# Power_Board.net
KiCad netlist of a schematic drawn in EAGLE
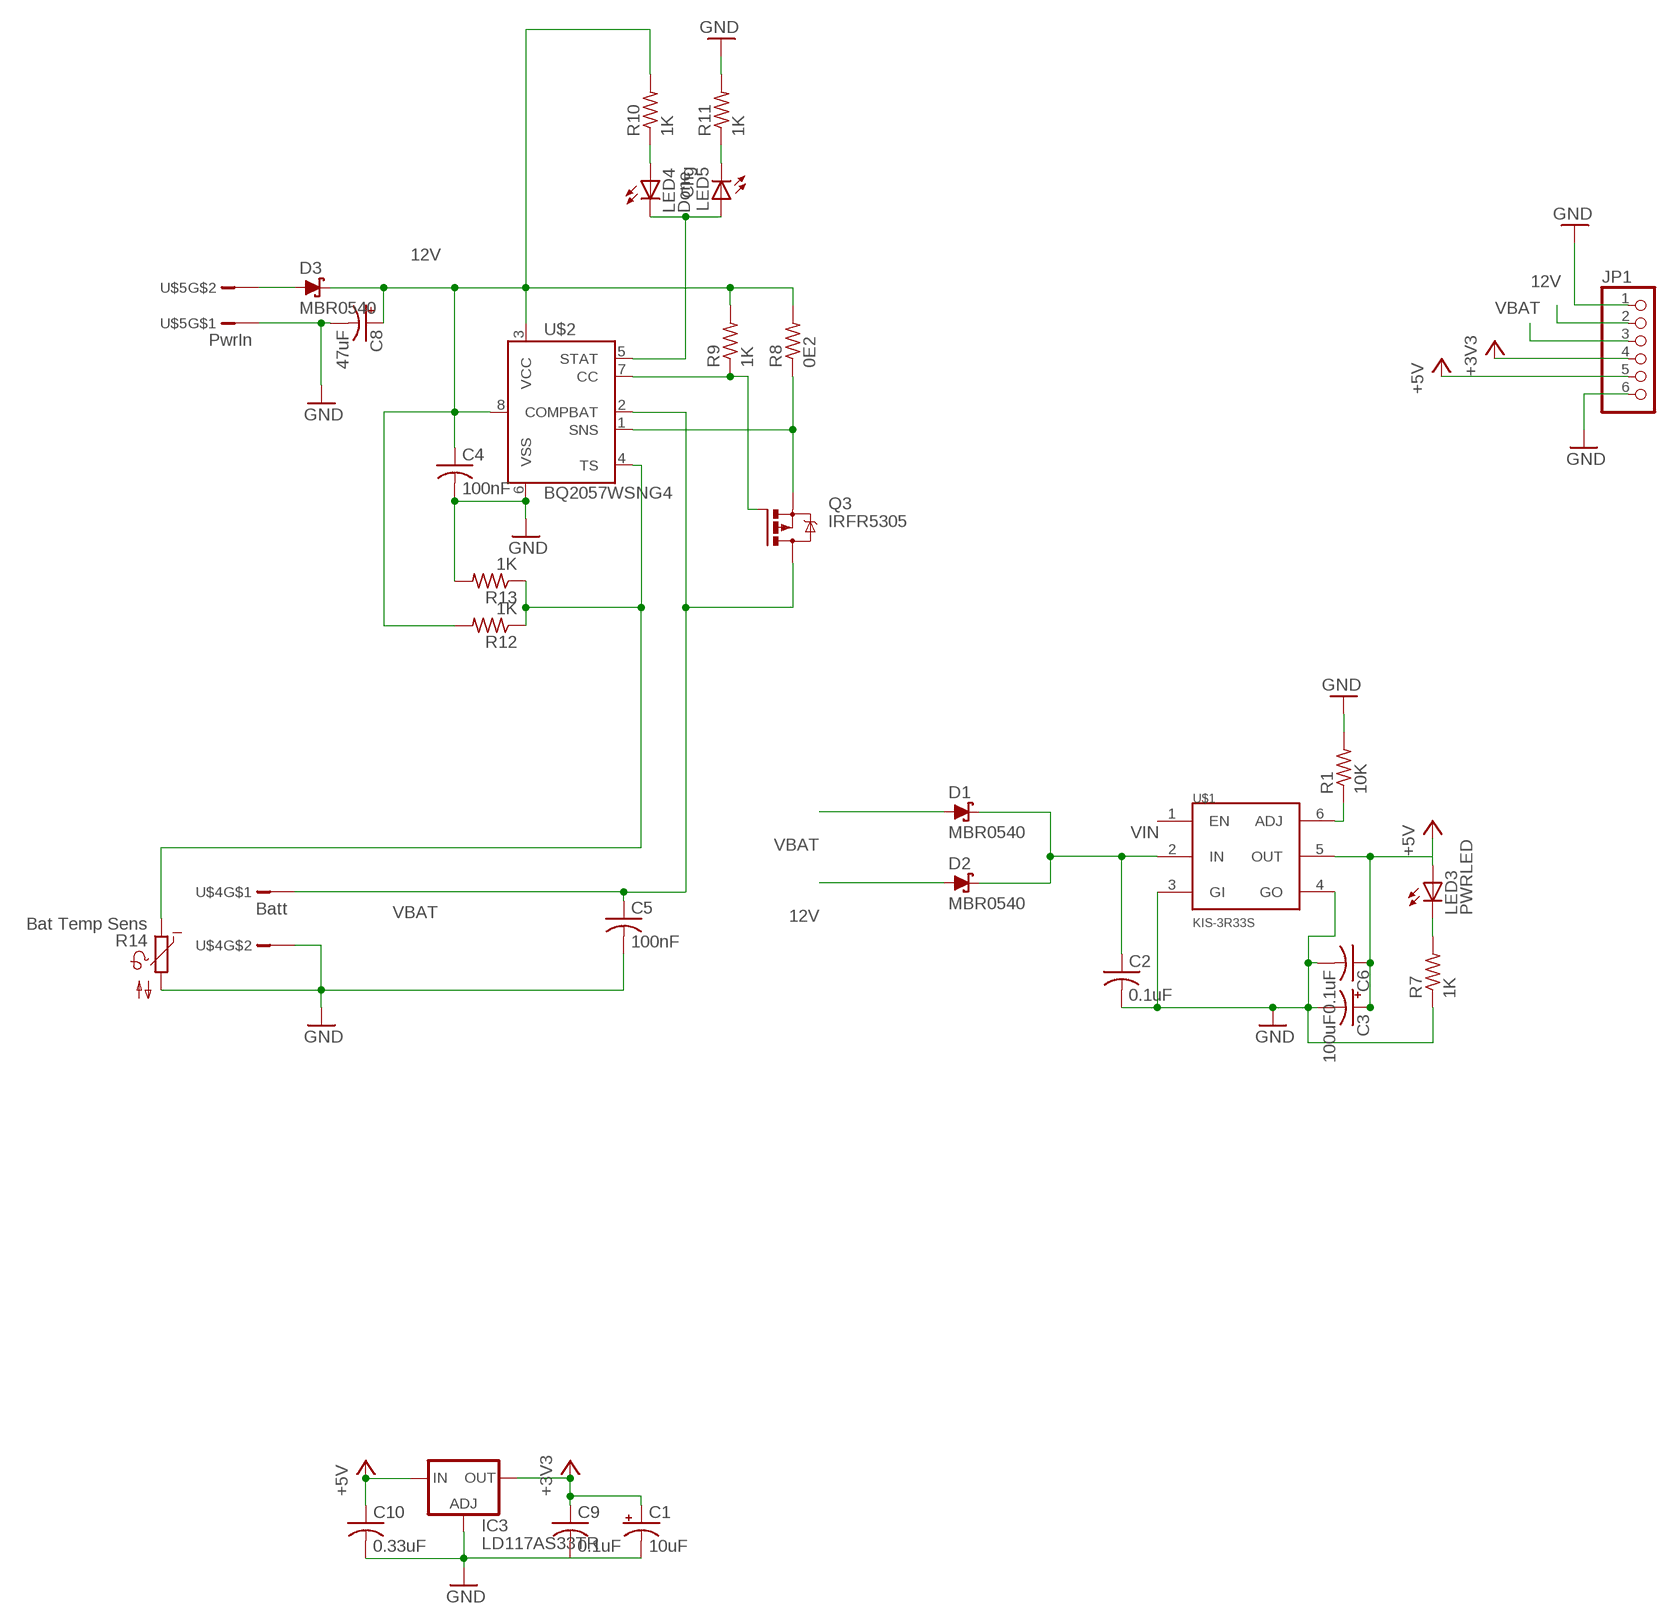
[diagram p0: schematic, sheet 1]

(export (version "E")
  (design (tool "Eeschema 10.0.6"))
  (components
    (comp (ref "C1")
      (value "10uF")
      (footprint "eagle-import:E2,5-7")
      (libsource (lib "eagle-import") (part "CPOL-USE2.5-7"))
    )
    (comp (ref "C2")
      (value "0.1uF")
      (footprint "eagle-import:C0805K")
      (libsource (lib "eagle-import") (part "C-USC0805K"))
    )
    (comp (ref "C3")
      (value "100uF")
      (footprint "eagle-import:E2,5-7")
      (libsource (lib "eagle-import") (part "CPOL-USE2.5-7"))
    )
    (comp (ref "C4")
      (value "100nF")
      (footprint "eagle-import:C0805K")
      (libsource (lib "eagle-import") (part "C-USC0805K"))
    )
    (comp (ref "C5")
      (value "100nF")
      (footprint "eagle-import:C0805K")
      (libsource (lib "eagle-import") (part "C-USC0805K"))
    )
    (comp (ref "C6")
      (value "0.1uF")
      (footprint "eagle-import:C0805K")
      (libsource (lib "eagle-import") (part "C-USC0805K"))
    )
    (comp (ref "C8")
      (value "47uF")
      (footprint "eagle-import:E2,5-7")
      (libsource (lib "eagle-import") (part "CPOL-USE2.5-7"))
    )
    (comp (ref "C9")
      (value "0.1uF")
      (footprint "eagle-import:C0805K")
      (libsource (lib "eagle-import") (part "C-USC0805K"))
    )
    (comp (ref "C10")
      (value "0.33uF")
      (footprint "eagle-import:C0805K")
      (libsource (lib "eagle-import") (part "C-USC0805K"))
    )
    (comp (ref "D1")
      (value "MBR0540")
      (footprint "eagle-import:SOD123")
      (libsource (lib "eagle-import") (part "MBR0540"))
    )
    (comp (ref "D2")
      (value "MBR0540")
      (footprint "eagle-import:SOD123")
      (libsource (lib "eagle-import") (part "MBR0540"))
    )
    (comp (ref "D3")
      (value "MBR0540")
      (footprint "eagle-import:SOD123")
      (libsource (lib "eagle-import") (part "MBR0540"))
    )
    (comp (ref "IC3")
      (value "LD117AS33TR")
      (footprint "eagle-import:SOT223")
      (libsource (lib "eagle-import") (part "LD117A?S33TR"))
    )
    (comp (ref "JP1")
      (value "PINHD-1X6")
      (footprint "eagle-import:1X06")
      (libsource (lib "eagle-import") (part "PINHD-1X6"))
    )
    (comp (ref "LED3")
      (value "PWRLED")
      (footprint "eagle-import:CHIPLED_0805")
      (libsource (lib "eagle-import") (part "LEDCHIPLED_0805"))
    )
    (comp (ref "LED4")
      (value "Done")
      (footprint "eagle-import:CHIPLED_0805")
      (libsource (lib "eagle-import") (part "LEDCHIPLED_0805"))
    )
    (comp (ref "LED5")
      (value "Chg")
      (footprint "eagle-import:CHIPLED_0805")
      (libsource (lib "eagle-import") (part "LEDCHIPLED_0805"))
    )
    (comp (ref "Q3")
      (value "IRFR5305")
      (footprint "eagle-import:D-PAK_TO252AA")
      (libsource (lib "eagle-import") (part "IRF?5305R"))
    )
    (comp (ref "R1")
      (value "10K")
      (footprint "eagle-import:R0805")
      (libsource (lib "eagle-import") (part "R-US_R0805"))
    )
    (comp (ref "R7")
      (value "1K")
      (footprint "eagle-import:R0805")
      (libsource (lib "eagle-import") (part "R-US_R0805"))
    )
    (comp (ref "R8")
      (value "0E2")
      (footprint "eagle-import:M1206")
      (libsource (lib "eagle-import") (part "R-US_M1206"))
    )
    (comp (ref "R9")
      (value "1K")
      (footprint "eagle-import:R0805")
      (libsource (lib "eagle-import") (part "R-US_R0805"))
    )
    (comp (ref "R10")
      (value "1K")
      (footprint "eagle-import:R0805")
      (libsource (lib "eagle-import") (part "R-US_R0805"))
    )
    (comp (ref "R11")
      (value "1K")
      (footprint "eagle-import:R0805")
      (libsource (lib "eagle-import") (part "R-US_R0805"))
    )
    (comp (ref "R12")
      (value "1K")
      (footprint "eagle-import:R0805")
      (libsource (lib "eagle-import") (part "R-US_R0805"))
    )
    (comp (ref "R13")
      (value "1K")
      (footprint "eagle-import:R0805")
      (libsource (lib "eagle-import") (part "R-US_R0805"))
    )
    (comp (ref "R14")
      (value "Bat Temp Sens")
      (footprint "eagle-import:P640")
      (libsource (lib "eagle-import") (part "NTC640"))
    )
    (comp (ref "U$1")
      (value "KIS-3R33S")
      (footprint "eagle-import:KIS-3R33S")
      (libsource (lib "eagle-import") (part "KIS-3R33S"))
    )
    (comp (ref "U$2")
      (value "BQ2057WSNG4")
      (footprint "eagle-import:D_R-PDSO-G8")
      (libsource (lib "eagle-import") (part "BQ2057WSNG4"))
    )
    (comp (ref "U$4")
      (value "Batt")
      (footprint "eagle-import:PHR-2")
      (libsource (lib "eagle-import") (part "JST_PHR-2"))
    )
    (comp (ref "U$5")
      (value "PwrIn")
      (footprint "eagle-import:PHR-2")
      (libsource (lib "eagle-import") (part "JST_PHR-2"))
    )
  )
  (nets
    (net (code "1") (name "+3V3") (class "Default")
      (node (ref "C1") (pin "+") (pinfunction "+_+") (pintype "passive"))
      (node (ref "C9") (pin "1") (pinfunction "1_1") (pintype "passive"))
      (node (ref "IC3") (pin "4") (pinfunction "OUT_4") (pintype "passive"))
      (node (ref "JP1") (pin "4") (pinfunction "4_4") (pintype "passive"))
    )
    (net (code "2") (name "+5V") (class "Default")
      (node (ref "C10") (pin "1") (pinfunction "1_1") (pintype "passive"))
      (node (ref "C3") (pin "+") (pinfunction "+_+") (pintype "passive"))
      (node (ref "C6") (pin "1") (pinfunction "1_1") (pintype "passive"))
      (node (ref "IC3") (pin "3") (pinfunction "IN_3") (pintype "input"))
      (node (ref "JP1") (pin "5") (pinfunction "5_5") (pintype "passive"))
      (node (ref "LED3") (pin "A") (pinfunction "A_A") (pintype "passive"))
      (node (ref "U$1") (pin "5") (pinfunction "OUT_5") (pintype "bidirectional"))
    )
    (net (code "3") (name "/12V") (class "Default")
      (node (ref "C4") (pin "1") (pinfunction "1_1") (pintype "passive"))
      (node (ref "C8") (pin "+") (pinfunction "+_+") (pintype "passive"))
      (node (ref "D2") (pin "A") (pinfunction "A_A") (pintype "passive"))
      (node (ref "D3") (pin "C") (pinfunction "C_C") (pintype "passive"))
      (node (ref "JP1") (pin "2") (pinfunction "2_2") (pintype "passive"))
      (node (ref "R10") (pin "2") (pinfunction "2_2") (pintype "passive"))
      (node (ref "R12") (pin "2") (pinfunction "2_2") (pintype "passive"))
      (node (ref "R8") (pin "2") (pinfunction "2_2") (pintype "passive"))
      (node (ref "R9") (pin "2") (pinfunction "2_2") (pintype "passive"))
      (node (ref "U$2") (pin "3") (pinfunction "VCC_3") (pintype "input"))
      (node (ref "U$2") (pin "8") (pinfunction "COMP_8") (pintype "input"))
    )
    (net (code "4") (name "/VBAT") (class "Default")
      (node (ref "C5") (pin "1") (pinfunction "1_1") (pintype "passive"))
      (node (ref "D1") (pin "A") (pinfunction "A_A") (pintype "passive"))
      (node (ref "JP1") (pin "3") (pinfunction "3_3") (pintype "passive"))
      (node (ref "Q3") (pin "4") (pinfunction "D_4") (pintype "passive"))
      (node (ref "U$2") (pin "2") (pinfunction "BAT_2") (pintype "input"))
      (node (ref "U$4") (pin "P$1") (pinfunction "1_P$1") (pintype "passive"))
    )
    (net (code "5") (name "/VIN") (class "Default")
      (node (ref "C2") (pin "1") (pinfunction "1_1") (pintype "passive"))
      (node (ref "D1") (pin "C") (pinfunction "C_C") (pintype "passive"))
      (node (ref "D2") (pin "C") (pinfunction "C_C") (pintype "passive"))
      (node (ref "U$1") (pin "2") (pinfunction "IN_2") (pintype "bidirectional"))
    )
    (net (code "6") (name "GND") (class "Default")
      (node (ref "C1") (pin "-") (pinfunction "-_-") (pintype "passive"))
      (node (ref "C10") (pin "2") (pinfunction "2_2") (pintype "passive"))
      (node (ref "C2") (pin "2") (pinfunction "2_2") (pintype "passive"))
      (node (ref "C3") (pin "-") (pinfunction "-_-") (pintype "passive"))
      (node (ref "C4") (pin "2") (pinfunction "2_2") (pintype "passive"))
      (node (ref "C5") (pin "2") (pinfunction "2_2") (pintype "passive"))
      (node (ref "C6") (pin "2") (pinfunction "2_2") (pintype "passive"))
      (node (ref "C8") (pin "-") (pinfunction "-_-") (pintype "passive"))
      (node (ref "C9") (pin "2") (pinfunction "2_2") (pintype "passive"))
      (node (ref "IC3") (pin "1") (pinfunction "ADJ_1") (pintype "input"))
      (node (ref "JP1") (pin "1") (pinfunction "1_1") (pintype "passive"))
      (node (ref "JP1") (pin "6") (pinfunction "6_6") (pintype "passive"))
      (node (ref "R1") (pin "2") (pinfunction "2_2") (pintype "passive"))
      (node (ref "R11") (pin "2") (pinfunction "2_2") (pintype "passive"))
      (node (ref "R13") (pin "2") (pinfunction "2_2") (pintype "passive"))
      (node (ref "R14") (pin "2") (pinfunction "2_2") (pintype "passive"))
      (node (ref "R7") (pin "1") (pinfunction "1_1") (pintype "passive"))
      (node (ref "U$1") (pin "3") (pinfunction "GI_3") (pintype "power_in"))
      (node (ref "U$1") (pin "4") (pinfunction "GO_4") (pintype "power_in"))
      (node (ref "U$2") (pin "6") (pinfunction "VSS_6") (pintype "power_in"))
      (node (ref "U$4") (pin "P$2") (pinfunction "1_P$2") (pintype "passive"))
      (node (ref "U$5") (pin "P$1") (pinfunction "1_P$1") (pintype "passive"))
    )
    (net (code "7") (name "Net-(LED3-PadC)") (class "Default")
      (node (ref "LED3") (pin "C") (pinfunction "C_C") (pintype "passive"))
      (node (ref "R7") (pin "2") (pinfunction "2_2") (pintype "passive"))
    )
    (net (code "8") (name "Net-(LED4-PadA)") (class "Default")
      (node (ref "LED4") (pin "A") (pinfunction "A_A") (pintype "passive"))
      (node (ref "R10") (pin "1") (pinfunction "1_1") (pintype "passive"))
    )
    (net (code "9") (name "Net-(LED5-PadC)") (class "Default")
      (node (ref "LED5") (pin "C") (pinfunction "C_C") (pintype "passive"))
      (node (ref "R11") (pin "1") (pinfunction "1_1") (pintype "passive"))
    )
    (net (code "10") (name "Net-(Q3-G)") (class "Default")
      (node (ref "Q3") (pin "1") (pinfunction "G_1") (pintype "passive"))
      (node (ref "R9") (pin "1") (pinfunction "1_1") (pintype "passive"))
      (node (ref "U$2") (pin "7") (pinfunction "CC_7") (pintype "output"))
    )
    (net (code "11") (name "Net-(Q3-S)") (class "Default")
      (node (ref "Q3") (pin "3") (pinfunction "S_3") (pintype "passive"))
      (node (ref "R8") (pin "1") (pinfunction "1_1") (pintype "passive"))
      (node (ref "U$2") (pin "1") (pinfunction "SNS_1") (pintype "input"))
    )
    (net (code "12") (name "Net-(U$1-ADJ)") (class "Default")
      (node (ref "R1") (pin "1") (pinfunction "1_1") (pintype "passive"))
      (node (ref "U$1") (pin "6") (pinfunction "ADJ_6") (pintype "bidirectional"))
    )
    (net (code "13") (name "Net-(U$2-STAT)") (class "Default")
      (node (ref "LED4") (pin "C") (pinfunction "C_C") (pintype "passive"))
      (node (ref "LED5") (pin "A") (pinfunction "A_A") (pintype "passive"))
      (node (ref "U$2") (pin "5") (pinfunction "STAT_5") (pintype "output"))
    )
    (net (code "14") (name "Net-(U$2-TS)") (class "Default")
      (node (ref "R12") (pin "1") (pinfunction "1_1") (pintype "passive"))
      (node (ref "R13") (pin "1") (pinfunction "1_1") (pintype "passive"))
      (node (ref "R14") (pin "1") (pinfunction "1_1") (pintype "passive"))
      (node (ref "U$2") (pin "4") (pinfunction "TS_4") (pintype "input"))
    )
    (net (code "15") (name "Net-(U$5B-1)") (class "Default")
      (node (ref "D3") (pin "A") (pinfunction "A_A") (pintype "passive"))
      (node (ref "U$5") (pin "P$2") (pinfunction "1_P$2") (pintype "passive"))
    )
    (net (code "16") (name "unconnected-(U$1-EN-Pad1)") (class "Default")
      (node (ref "U$1") (pin "1") (pinfunction "EN_1") (pintype "bidirectional"))
    )
  )
)
